# Shield_Amir_EDO_V_0_2_1.net
KiCad netlist of a schematic drawn in EasyEDA
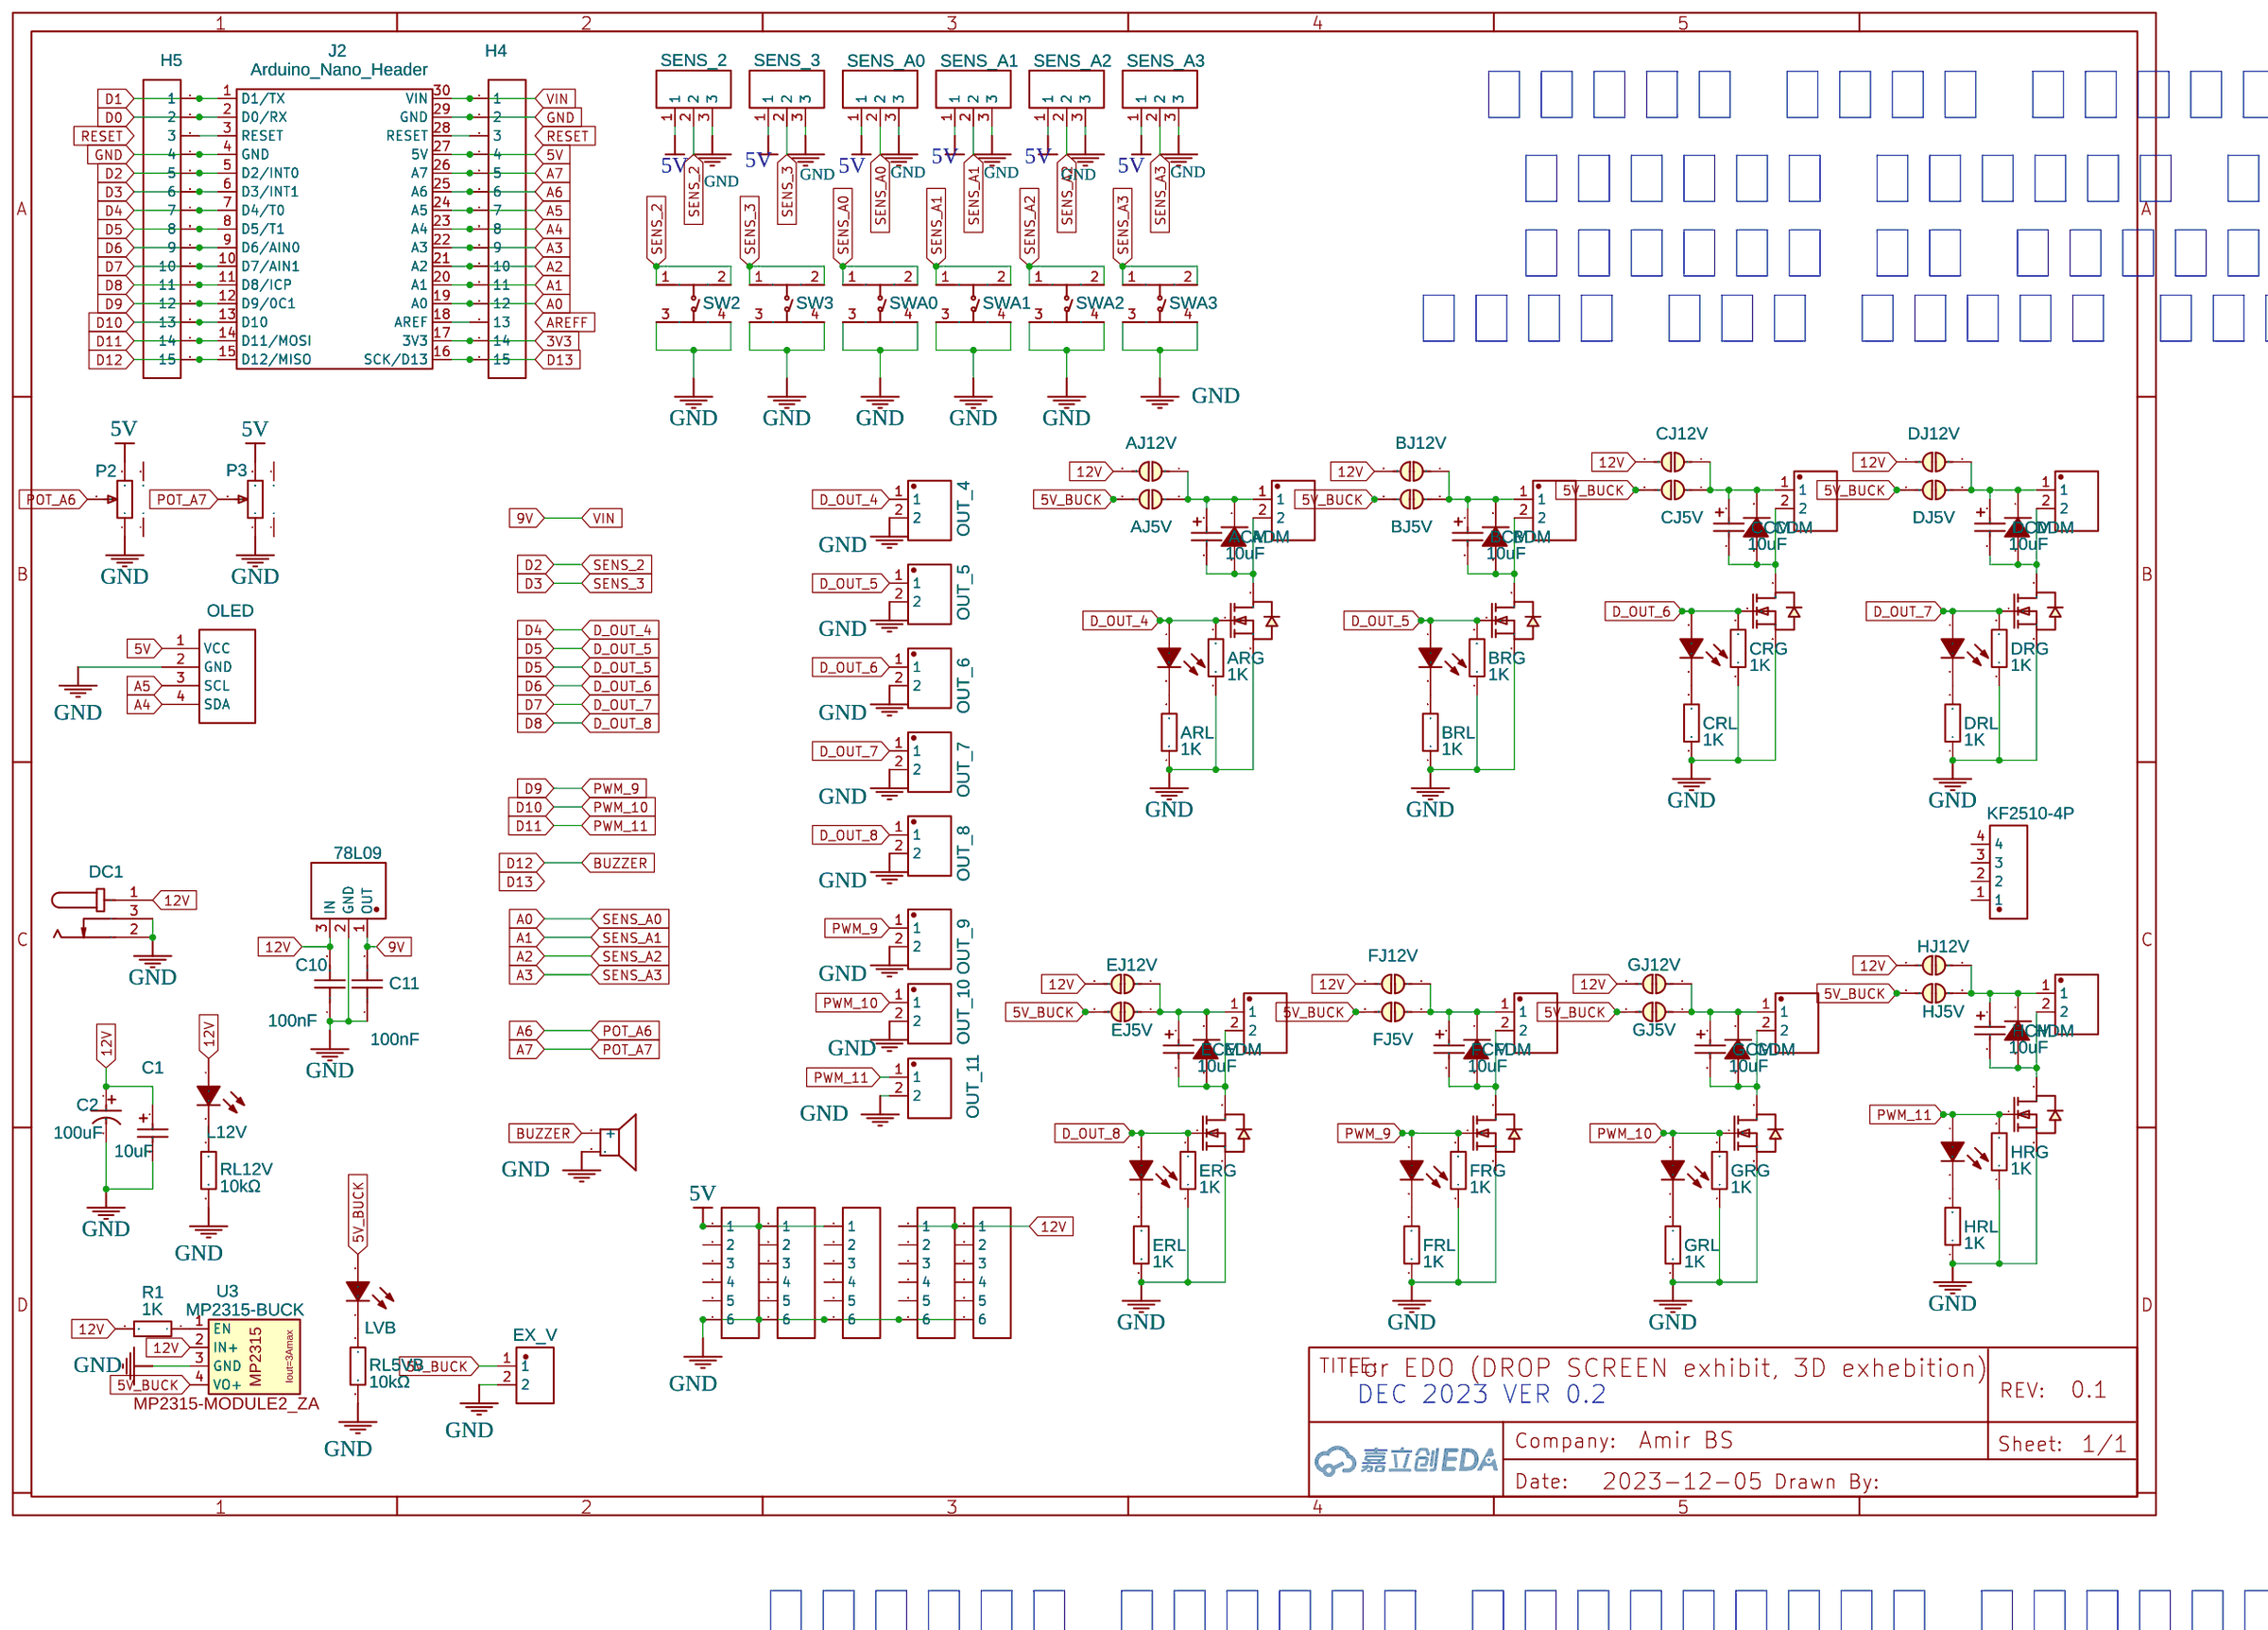
[diagram p0: schematic sheet]

(export (version "E")
  (design (tool "Eeschema 10.0.6"))
  (components
    (comp (ref "ACM")
      (value "10uF")
      (fields (field (name "Manufacturer Part") "TAJA106K016RNJ") (field (name "Manufacturer") "Kyocera AVX"))
      (libsource (lib "") (part "TAJA106K016RNJ"))
    )
    (comp (ref "ACON")
      (value "KF2510-2A")
      (fields (field (name "BOM_Supplier Part") "C27543"))
      (libsource (lib "") (part "KF2510-2A_5"))
    )
    (comp (ref "ADM")
      (value "1N4007")
      (fields (field (name "BOM_Manufacturer Part") "1N4007F") (field (name "BOM_Supplier Part") "C110856"))
      (libsource (lib "") (part "1N4007F_4"))
    )
    (comp (ref "AJ5V") (value "JUMPER-SMT_2") (libsource (lib "") (part "JUMPER-SMT_2_1")))
    (comp (ref "AJ12V") (value "JUMPER-SMT_2") (libsource (lib "") (part "JUMPER-SMT_2_3")))
    (comp (ref "ALD")
      (value "LED")
      (fields
        (field (name "BOM_Manufacturer Part") "19-217/BHC-ZL1M2RY/3T")
        (field (name "BOM_Supplier Part") "C72041")
      )
      (libsource (lib "") (part "19-217/BHC-ZL1M2RY/3T_3"))
    )
    (comp (ref "AQ")
      (value "Q")
      (fields (field (name "BOM_Manufacturer Part") "AO3400") (field (name "BOM_Supplier Part") "C5224189"))
      (libsource (lib "") (part "JSM2302_2"))
    )
    (comp (ref "ARG")
      (value "1K")
      (fields
        (field (name "BOM_Manufacturer Part") "0603WAF1001T5E")
        (field (name "BOM_Supplier Part") "C21190")
      )
      (libsource (lib "") (part "0603WAF1001T5E_13"))
    )
    (comp (ref "ARL")
      (value "1K")
      (fields
        (field (name "BOM_Manufacturer Part") "0603WAF1001T5E")
        (field (name "BOM_Supplier Part") "C21190")
      )
      (libsource (lib "") (part "0603WAF1001T5E_5"))
    )
    (comp (ref "BCM")
      (value "10uF")
      (fields (field (name "Manufacturer Part") "TAJA106K016RNJ") (field (name "Manufacturer") "Kyocera AVX"))
      (libsource (lib "") (part "TAJA106K016RNJ_3"))
    )
    (comp (ref "BCON")
      (value "KF2510-2A")
      (fields (field (name "BOM_Supplier Part") "C27543"))
      (libsource (lib "") (part "KF2510-2A_1"))
    )
    (comp (ref "BDM")
      (value "1N4007")
      (fields (field (name "BOM_Manufacturer Part") "1N4007F") (field (name "BOM_Supplier Part") "C110856"))
      (libsource (lib "") (part "1N4007F_3"))
    )
    (comp (ref "BJ5V") (value "JUMPER-SMT_2") (libsource (lib "") (part "JUMPER-SMT_2_6")))
    (comp (ref "BJ12V") (value "JUMPER-SMT_2") (libsource (lib "") (part "JUMPER-SMT_2_8")))
    (comp (ref "BLD")
      (value "LED")
      (fields
        (field (name "BOM_Manufacturer Part") "19-217/BHC-ZL1M2RY/3T")
        (field (name "BOM_Supplier Part") "C72041")
      )
      (libsource (lib "") (part "19-217/BHC-ZL1M2RY/3T_5"))
    )
    (comp (ref "BQ")
      (value "Q")
      (fields (field (name "BOM_Manufacturer Part") "AO3400") (field (name "BOM_Supplier Part") "C5224189"))
      (libsource (lib "") (part "JSM2302"))
    )
    (comp (ref "BRG")
      (value "1K")
      (fields
        (field (name "BOM_Manufacturer Part") "0603WAF1001T5E")
        (field (name "BOM_Supplier Part") "C21190")
      )
      (libsource (lib "") (part "0603WAF1001T5E_9"))
    )
    (comp (ref "BRL")
      (value "1K")
      (fields
        (field (name "BOM_Manufacturer Part") "0603WAF1001T5E")
        (field (name "BOM_Supplier Part") "C21190")
      )
      (libsource (lib "") (part "0603WAF1001T5E_12"))
    )
    (comp (ref "BUZZER1")
      (value "BUZZER-12X9")
      (fields (field (name "Manufacturer Part") "buzzer-12X9"))
      (libsource (lib "") (part "BUZZER-12X9"))
    )
    (comp (ref "C1")
      (value "10uF")
      (fields (field (name "Manufacturer Part") "TAJA106K016RNJ") (field (name "Manufacturer") "Kyocera AVX"))
      (libsource (lib "") (part "TAJA106K016RNJ_4"))
    )
    (comp (ref "C2")
      (value "100uF")
      (fields
        (field (name "Manufacturer Part") "KM107M035E11RR0VH2FP0")
        (field (name "Manufacturer") "CX(承兴)")
      )
      (libsource (lib "") (part "100uF 35V 6.3*11"))
    )
    (comp (ref "C10")
      (value "100nF")
      (fields
        (field (name "Manufacturer Part") "CC0603KRX7R9BB104")
        (field (name "Manufacturer") "YAGEO(国巨)")
      )
      (libsource (lib "") (part "CC0603KRX7R9BB104"))
    )
    (comp (ref "C11")
      (value "100nF")
      (fields
        (field (name "Manufacturer Part") "CC0603KRX7R9BB104")
        (field (name "Manufacturer") "YAGEO(国巨)")
      )
      (libsource (lib "") (part "CC0603KRX7R9BB104"))
    )
    (comp (ref "CCM")
      (value "10uF")
      (fields (field (name "Manufacturer Part") "TAJA106K016RNJ") (field (name "Manufacturer") "Kyocera AVX"))
      (libsource (lib "") (part "TAJA106K016RNJ_8"))
    )
    (comp (ref "CCON")
      (value "KF2510-2A")
      (fields (field (name "BOM_Supplier Part") "C27543"))
      (libsource (lib "") (part "KF2510-2A"))
    )
    (comp (ref "CDM")
      (value "1N4007")
      (fields (field (name "BOM_Manufacturer Part") "1N4007F") (field (name "BOM_Supplier Part") "C110856"))
      (libsource (lib "") (part "1N4007F_1"))
    )
    (comp (ref "CJ5V") (value "JUMPER-SMT_2") (libsource (lib "") (part "JUMPER-SMT_2_15")))
    (comp (ref "CJ12V") (value "JUMPER-SMT_2") (libsource (lib "") (part "JUMPER-SMT_2")))
    (comp (ref "CLD")
      (value "LED")
      (fields
        (field (name "BOM_Manufacturer Part") "19-217/BHC-ZL1M2RY/3T")
        (field (name "BOM_Supplier Part") "C72041")
      )
      (libsource (lib "") (part "19-217/BHC-ZL1M2RY/3T_2"))
    )
    (comp (ref "CQ")
      (value "Q")
      (fields (field (name "BOM_Manufacturer Part") "AO3400") (field (name "BOM_Supplier Part") "C5224189"))
      (libsource (lib "") (part "JSM2302_1"))
    )
    (comp (ref "CRG")
      (value "1K")
      (fields
        (field (name "BOM_Manufacturer Part") "0603WAF1001T5E")
        (field (name "BOM_Supplier Part") "C21190")
      )
      (libsource (lib "") (part "0603WAF1001T5E_16"))
    )
    (comp (ref "CRL")
      (value "1K")
      (fields
        (field (name "BOM_Manufacturer Part") "0603WAF1001T5E")
        (field (name "BOM_Supplier Part") "C21190")
      )
      (libsource (lib "") (part "0603WAF1001T5E_15"))
    )
    (comp (ref "DC1")
      (value "DC")
      (fields
        (field (name "BOM_Manufacturer Part") "DC005-2.0MM")
        (field (name "BOM_Supplier Part") "C111567")
      )
      (libsource (lib "") (part "DC005-2.0MM"))
    )
    (comp (ref "DCM")
      (value "10uF")
      (fields (field (name "Manufacturer Part") "TAJA106K016RNJ") (field (name "Manufacturer") "Kyocera AVX"))
      (libsource (lib "") (part "TAJA106K016RNJ_1"))
    )
    (comp (ref "DCON")
      (value "KF2510-2A")
      (fields (field (name "BOM_Supplier Part") "C27543"))
      (libsource (lib "") (part "KF2510-2A_3"))
    )
    (comp (ref "DDM")
      (value "1N4007")
      (fields (field (name "BOM_Manufacturer Part") "1N4007F") (field (name "BOM_Supplier Part") "C110856"))
      (libsource (lib "") (part "1N4007F_2"))
    )
    (comp (ref "DJ5V") (value "JUMPER-SMT_2") (libsource (lib "") (part "JUMPER-SMT_2_12")))
    (comp (ref "DJ12V") (value "JUMPER-SMT_2") (libsource (lib "") (part "JUMPER-SMT_2_7")))
    (comp (ref "DLD")
      (value "LED")
      (fields
        (field (name "BOM_Manufacturer Part") "19-217/BHC-ZL1M2RY/3T")
        (field (name "BOM_Supplier Part") "C72041")
      )
      (libsource (lib "") (part "19-217/BHC-ZL1M2RY/3T_6"))
    )
    (comp (ref "DQ")
      (value "Q")
      (fields (field (name "BOM_Manufacturer Part") "AO3400") (field (name "BOM_Supplier Part") "C5224189"))
      (libsource (lib "") (part "JSM2302_7"))
    )
    (comp (ref "DRG")
      (value "1K")
      (fields
        (field (name "BOM_Manufacturer Part") "0603WAF1001T5E")
        (field (name "BOM_Supplier Part") "C21190")
      )
      (libsource (lib "") (part "0603WAF1001T5E_6"))
    )
    (comp (ref "DRL")
      (value "1K")
      (fields
        (field (name "BOM_Manufacturer Part") "0603WAF1001T5E")
        (field (name "BOM_Supplier Part") "C21190")
      )
      (libsource (lib "") (part "0603WAF1001T5E_10"))
    )
    (comp (ref "ECM")
      (value "10uF")
      (fields (field (name "Manufacturer Part") "TAJA106K016RNJ") (field (name "Manufacturer") "Kyocera AVX"))
      (libsource (lib "") (part "TAJA106K016RNJ_7"))
    )
    (comp (ref "ECON")
      (value "KF2510-2A")
      (fields (field (name "BOM_Supplier Part") "C27543"))
      (libsource (lib "") (part "KF2510-2A_6"))
    )
    (comp (ref "EDM")
      (value "1N4007")
      (fields (field (name "BOM_Manufacturer Part") "1N4007F") (field (name "BOM_Supplier Part") "C110856"))
      (libsource (lib "") (part "1N4007F_5"))
    )
    (comp (ref "EJ5V") (value "JUMPER-SMT_2") (libsource (lib "") (part "JUMPER-SMT_2_11")))
    (comp (ref "EJ12V") (value "JUMPER-SMT_2") (libsource (lib "") (part "JUMPER-SMT_2_2")))
    (comp (ref "ELD")
      (value "LED")
      (fields
        (field (name "BOM_Manufacturer Part") "19-217/BHC-ZL1M2RY/3T")
        (field (name "BOM_Supplier Part") "C72041")
      )
      (libsource (lib "") (part "19-217/BHC-ZL1M2RY/3T_9"))
    )
    (comp (ref "EQ")
      (value "Q")
      (fields (field (name "BOM_Manufacturer Part") "AO3400") (field (name "BOM_Supplier Part") "C5224189"))
      (libsource (lib "") (part "JSM2302_4"))
    )
    (comp (ref "ERG")
      (value "1K")
      (fields
        (field (name "BOM_Manufacturer Part") "0603WAF1001T5E")
        (field (name "BOM_Supplier Part") "C21190")
      )
      (libsource (lib "") (part "0603WAF1001T5E_8"))
    )
    (comp (ref "ERL")
      (value "1K")
      (fields
        (field (name "BOM_Manufacturer Part") "0603WAF1001T5E")
        (field (name "BOM_Supplier Part") "C21190")
      )
      (libsource (lib "") (part "0603WAF1001T5E_4"))
    )
    (comp (ref "EX_V")
      (value "EX_V")
      (fields
        (field (name "Manufacturer Part") "WJ306V-5.0-2P-14-00A")
        (field (name "Manufacturer") "KANGNEX(康奈克斯电气)")
      )
      (libsource (lib "") (part "WJ306V-5.0-2P-14-00A"))
    )
    (comp (ref "FCM")
      (value "10uF")
      (fields (field (name "Manufacturer Part") "TAJA106K016RNJ") (field (name "Manufacturer") "Kyocera AVX"))
      (libsource (lib "") (part "TAJA106K016RNJ_2"))
    )
    (comp (ref "FCON")
      (value "KF2510-2A")
      (fields (field (name "BOM_Supplier Part") "C27543"))
      (libsource (lib "") (part "KF2510-2A_8"))
    )
    (comp (ref "FDM")
      (value "1N4007")
      (fields (field (name "BOM_Manufacturer Part") "1N4007F") (field (name "BOM_Supplier Part") "C110856"))
      (libsource (lib "") (part "1N4007F_6"))
    )
    (comp (ref "FJ5V") (value "JUMPER-SMT_2") (libsource (lib "") (part "JUMPER-SMT_2_10")))
    (comp (ref "FJ12V") (value "JUMPER-SMT_2") (libsource (lib "") (part "JUMPER-SMT_2_4")))
    (comp (ref "FLD")
      (value "LED")
      (fields
        (field (name "BOM_Manufacturer Part") "19-217/BHC-ZL1M2RY/3T")
        (field (name "BOM_Supplier Part") "C72041")
      )
      (libsource (lib "") (part "19-217/BHC-ZL1M2RY/3T"))
    )
    (comp (ref "FQ")
      (value "Q")
      (fields (field (name "BOM_Manufacturer Part") "AO3400") (field (name "BOM_Supplier Part") "C5224189"))
      (libsource (lib "") (part "JSM2302_6"))
    )
    (comp (ref "FRG")
      (value "1K")
      (fields
        (field (name "BOM_Manufacturer Part") "0603WAF1001T5E")
        (field (name "BOM_Supplier Part") "C21190")
      )
      (libsource (lib "") (part "0603WAF1001T5E_11"))
    )
    (comp (ref "FRL")
      (value "1K")
      (fields
        (field (name "BOM_Manufacturer Part") "0603WAF1001T5E")
        (field (name "BOM_Supplier Part") "C21190")
      )
      (libsource (lib "") (part "0603WAF1001T5E_1"))
    )
    (comp (ref "GCM")
      (value "10uF")
      (fields (field (name "Manufacturer Part") "TAJA106K016RNJ") (field (name "Manufacturer") "Kyocera AVX"))
      (libsource (lib "") (part "TAJA106K016RNJ_6"))
    )
    (comp (ref "GCON")
      (value "KF2510-2A")
      (fields (field (name "BOM_Supplier Part") "C27543"))
      (libsource (lib "") (part "KF2510-2A_4"))
    )
    (comp (ref "GDM")
      (value "1N4007")
      (fields (field (name "BOM_Manufacturer Part") "1N4007F") (field (name "BOM_Supplier Part") "C110856"))
      (libsource (lib "") (part "1N4007F"))
    )
    (comp (ref "GJ5V") (value "JUMPER-SMT_2") (libsource (lib "") (part "JUMPER-SMT_2_13")))
    (comp (ref "GJ12V") (value "JUMPER-SMT_2") (libsource (lib "") (part "JUMPER-SMT_2_9")))
    (comp (ref "GLD")
      (value "LED")
      (fields
        (field (name "BOM_Manufacturer Part") "19-217/BHC-ZL1M2RY/3T")
        (field (name "BOM_Supplier Part") "C72041")
      )
      (libsource (lib "") (part "19-217/BHC-ZL1M2RY/3T_7"))
    )
    (comp (ref "GQ")
      (value "Q")
      (fields (field (name "BOM_Manufacturer Part") "AO3400") (field (name "BOM_Supplier Part") "C5224189"))
      (libsource (lib "") (part "JSM2302_3"))
    )
    (comp (ref "GRG")
      (value "1K")
      (fields
        (field (name "BOM_Manufacturer Part") "0603WAF1001T5E")
        (field (name "BOM_Supplier Part") "C21190")
      )
      (libsource (lib "") (part "0603WAF1001T5E"))
    )
    (comp (ref "GRL")
      (value "1K")
      (fields
        (field (name "BOM_Manufacturer Part") "0603WAF1001T5E")
        (field (name "BOM_Supplier Part") "C21190")
      )
      (libsource (lib "") (part "0603WAF1001T5E_2"))
    )
    (comp (ref "H1")
      (value "HDR-F-2.54_1x6")
      (fields (field (name "BOM_Supplier Part") "C40877"))
      (libsource (lib "") (part "HDR-F-2.54_1x6"))
    )
    (comp (ref "H2")
      (value "HDR-F-2.54_1x6")
      (fields (field (name "BOM_Supplier Part") "C40877"))
      (libsource (lib "") (part "HDR-F-2.54_1x6"))
    )
    (comp (ref "H3")
      (value "HDR-F-2.54_1x6")
      (fields (field (name "BOM_Supplier Part") "C40877"))
      (libsource (lib "") (part "HDR-F-2.54_1x6"))
    )
    (comp (ref "H4")
      (value "HDR-F-2.54_1x15")
      (fields (field (name "BOM_Supplier Part") "C124408"))
      (libsource (lib "") (part "HDR-F-2.54_1x15"))
    )
    (comp (ref "H5")
      (value "HDR-F-2.54_1x15")
      (fields (field (name "BOM_Supplier Part") "C124408"))
      (libsource (lib "") (part "HDR-F-2.54_1x15_1"))
    )
    (comp (ref "H6")
      (value "HDR-F-2.54_1x6")
      (fields (field (name "BOM_Supplier Part") "C40877"))
      (libsource (lib "") (part "HDR-F-2.54_1x6"))
    )
    (comp (ref "H11")
      (value "HDR-F-2.54_1x6")
      (fields (field (name "BOM_Supplier Part") "C40877"))
      (libsource (lib "") (part "HDR-F-2.54_1x6"))
    )
    (comp (ref "HCM")
      (value "10uF")
      (fields (field (name "Manufacturer Part") "TAJA106K016RNJ") (field (name "Manufacturer") "Kyocera AVX"))
      (libsource (lib "") (part "TAJA106K016RNJ_5"))
    )
    (comp (ref "HCON")
      (value "KF2510-2A")
      (fields (field (name "BOM_Supplier Part") "C27543"))
      (libsource (lib "") (part "KF2510-2A_7"))
    )
    (comp (ref "HDM")
      (value "1N4007")
      (fields (field (name "BOM_Manufacturer Part") "1N4007F") (field (name "BOM_Supplier Part") "C110856"))
      (libsource (lib "") (part "1N4007F_7"))
    )
    (comp (ref "HJ5V") (value "JUMPER-SMT_2") (libsource (lib "") (part "JUMPER-SMT_2_5")))
    (comp (ref "HJ12V") (value "JUMPER-SMT_2") (libsource (lib "") (part "JUMPER-SMT_2_14")))
    (comp (ref "HLD")
      (value "LED")
      (fields
        (field (name "BOM_Manufacturer Part") "19-217/BHC-ZL1M2RY/3T")
        (field (name "BOM_Supplier Part") "C72041")
      )
      (libsource (lib "") (part "19-217/BHC-ZL1M2RY/3T_4"))
    )
    (comp (ref "HQ")
      (value "Q")
      (fields (field (name "BOM_Manufacturer Part") "AO3400") (field (name "BOM_Supplier Part") "C5224189"))
      (libsource (lib "") (part "JSM2302_5"))
    )
    (comp (ref "HRG")
      (value "1K")
      (fields
        (field (name "BOM_Manufacturer Part") "0603WAF1001T5E")
        (field (name "BOM_Supplier Part") "C21190")
      )
      (libsource (lib "") (part "0603WAF1001T5E_7"))
    )
    (comp (ref "HRL")
      (value "1K")
      (fields
        (field (name "BOM_Manufacturer Part") "0603WAF1001T5E")
        (field (name "BOM_Supplier Part") "C21190")
      )
      (libsource (lib "") (part "0603WAF1001T5E_14"))
    )
    (comp (ref "J2") (value "Arduino_Nano_Header") (libsource (lib "") (part "Arduino_Nano_Header")))
    (comp (ref "L12V")
      (value "LED")
      (fields
        (field (name "BOM_Manufacturer Part") "19-217/BHC-ZL1M2RY/3T")
        (field (name "BOM_Supplier Part") "C72041")
      )
      (libsource (lib "") (part "19-217/BHC-ZL1M2RY/3T_1"))
    )
    (comp (ref "LVB")
      (value "LED")
      (fields
        (field (name "BOM_Manufacturer Part") "19-217/BHC-ZL1M2RY/3T")
        (field (name "BOM_Supplier Part") "C72041")
      )
      (libsource (lib "") (part "19-217/BHC-ZL1M2RY/3T_8"))
    )
    (comp (ref "OLED")
      (value "1.3 inch OLED SSH1106 I2C 128x64 copy")
      (libsource (lib "") (part "1.3 inch OLED SSH1106 I2C 128x64 copy"))
    )
    (comp (ref "OUT_4")
      (value "KF2510-2A")
      (fields (field (name "BOM_Supplier Part") "C27543"))
      (libsource (lib "") (part "KF2510-2A_2"))
    )
    (comp (ref "OUT_5")
      (value "KF2510-2A")
      (fields (field (name "BOM_Supplier Part") "C27543"))
      (libsource (lib "") (part "KF2510-2A_2"))
    )
    (comp (ref "OUT_6")
      (value "KF2510-2A")
      (fields (field (name "BOM_Supplier Part") "C27543"))
      (libsource (lib "") (part "KF2510-2A_2"))
    )
    (comp (ref "OUT_7")
      (value "KF2510-2A")
      (fields (field (name "BOM_Supplier Part") "C27543"))
      (libsource (lib "") (part "KF2510-2A_2"))
    )
    (comp (ref "OUT_8")
      (value "KF2510-2A")
      (fields (field (name "BOM_Supplier Part") "C27543"))
      (libsource (lib "") (part "KF2510-2A_2"))
    )
    (comp (ref "OUT_9")
      (value "KF2510-2A")
      (fields (field (name "BOM_Supplier Part") "C27543"))
      (libsource (lib "") (part "KF2510-2A_2"))
    )
    (comp (ref "OUT_10")
      (value "KF2510-2A")
      (fields (field (name "BOM_Supplier Part") "C27543"))
      (libsource (lib "") (part "KF2510-2A_2"))
    )
    (comp (ref "OUT_11")
      (value "KF2510-2A")
      (fields (field (name "BOM_Supplier Part") "C27543"))
      (libsource (lib "") (part "KF2510-2A_2"))
    )
    (comp (ref "P2")
      (value "长柄旋转电位器")
      (fields (field (name "BOM_Supplier Part") "C2874842"))
      (libsource (lib "") (part "长柄旋转电位器"))
    )
    (comp (ref "P3")
      (value "长柄旋转电位器")
      (fields (field (name "BOM_Supplier Part") "C2874842"))
      (libsource (lib "") (part "长柄旋转电位器"))
    )
    (comp (ref "R1")
      (value "1K")
      (fields
        (field (name "BOM_Manufacturer Part") "0603WAF1001T5E")
        (field (name "BOM_Supplier Part") "C21190")
      )
      (libsource (lib "") (part "0603WAF1001T5E_3"))
    )
    (comp (ref "RL5VB")
      (value "10kΩ")
      (fields
        (field (name "BOM_Manufacturer Part") "0603WAF1002T5E")
        (field (name "BOM_Supplier Part") "C25804")
      )
      (libsource (lib "") (part "0603WAF1002T5E_1"))
    )
    (comp (ref "RL12V")
      (value "10kΩ")
      (fields
        (field (name "BOM_Manufacturer Part") "0603WAF1002T5E")
        (field (name "BOM_Supplier Part") "C25804")
      )
      (libsource (lib "") (part "0603WAF1002T5E"))
    )
    (comp (ref "SENS_2")
      (value "FK2510")
      (fields (field (name "Manufacturer Part") "2510-3A") (field (name "Manufacturer") "BOOMELE(博穆精密)"))
      (libsource (lib "") (part "kf2510_3A_1"))
    )
    (comp (ref "SENS_3")
      (value "FK2510")
      (fields (field (name "Manufacturer Part") "2510-3A") (field (name "Manufacturer") "BOOMELE(博穆精密)"))
      (libsource (lib "") (part "kf2510_3A_1"))
    )
    (comp (ref "SENS_A0")
      (value "FK2510")
      (fields (field (name "Manufacturer Part") "2510-3A") (field (name "Manufacturer") "BOOMELE(博穆精密)"))
      (libsource (lib "") (part "kf2510_3A"))
    )
    (comp (ref "SENS_A1")
      (value "FK2510")
      (fields (field (name "Manufacturer Part") "2510-3A") (field (name "Manufacturer") "BOOMELE(博穆精密)"))
      (libsource (lib "") (part "kf2510_3A"))
    )
    (comp (ref "SENS_A2")
      (value "FK2510")
      (fields (field (name "Manufacturer Part") "2510-3A") (field (name "Manufacturer") "BOOMELE(博穆精密)"))
      (libsource (lib "") (part "kf2510_3A"))
    )
    (comp (ref "SENS_A3")
      (value "FK2510")
      (fields (field (name "Manufacturer Part") "2510-3A") (field (name "Manufacturer") "BOOMELE(博穆精密)"))
      (libsource (lib "") (part "kf2510_3A"))
    )
    (comp (ref "SW2")
      (value "TC-6610-7-160G")
      (fields (field (name "Manufacturer") "HCTL(华灿天禄)"))
      (libsource (lib "") (part "TC-6610-7-160G_1"))
    )
    (comp (ref "SW3")
      (value "TC-6610-7-160G")
      (fields (field (name "Manufacturer") "HCTL(华灿天禄)"))
      (libsource (lib "") (part "TC-6610-7-160G_1"))
    )
    (comp (ref "SWA0")
      (value "TC-6610-7-160G")
      (fields (field (name "Manufacturer") "HCTL(华灿天禄)"))
      (libsource (lib "") (part "TC-6610-7-160G"))
    )
    (comp (ref "SWA1")
      (value "TC-6610-7-160G")
      (fields (field (name "Manufacturer") "HCTL(华灿天禄)"))
      (libsource (lib "") (part "TC-6610-7-160G"))
    )
    (comp (ref "SWA2")
      (value "TC-6610-7-160G")
      (fields (field (name "Manufacturer") "HCTL(华灿天禄)"))
      (libsource (lib "") (part "TC-6610-7-160G"))
    )
    (comp (ref "SWA3")
      (value "TC-6610-7-160G")
      (fields (field (name "Manufacturer") "HCTL(华灿天禄)"))
      (libsource (lib "") (part "TC-6610-7-160G"))
    )
    (comp (ref "U1")
      (value "KF2510-4P")
      (fields (field (name "BOM_Supplier Part") "C9900008392"))
      (libsource (lib "") (part "KF2510-4P"))
    )
    (comp (ref "U3") (value "MP2315-BUCK") (libsource (lib "") (part "MP2315-BUCK")))
    (comp (ref "U5")
      (value "78L09")
      (fields (field (name "Manufacturer Part") "78L09U 78L09") (field (name "Manufacturer") "CBI(创基)"))
      (libsource (lib "") (part "78L09U 78L09"))
    )
  )
  (nets
    (net (code "1") (name "3V3") (class "Default")
      (node (ref "H4") (pin "14") (pinfunction "14_14") (pintype "unspecified"))
      (node (ref "J2") (pin "17") (pinfunction "3V3_17") (pintype "unspecified"))
    )
    (net (code "2") (name "5V") (class "Default")
      (node (ref "H1") (pin "1") (pinfunction "1_1") (pintype "input"))
      (node (ref "H2") (pin "1") (pinfunction "1_1") (pintype "input"))
      (node (ref "H3") (pin "1") (pinfunction "1_1") (pintype "input"))
      (node (ref "H4") (pin "4") (pinfunction "4_4") (pintype "unspecified"))
      (node (ref "J2") (pin "27") (pinfunction "5V_27") (pintype "unspecified"))
      (node (ref "OLED") (pin "1") (pinfunction "VCC_1") (pintype "passive"))
      (node (ref "P2") (pin "3") (pinfunction "3_3") (pintype "input"))
      (node (ref "P3") (pin "3") (pinfunction "3_3") (pintype "input"))
      (node (ref "SENS_2") (pin "1") (pinfunction "1_1") (pintype "unspecified"))
      (node (ref "SENS_3") (pin "1") (pinfunction "1_1") (pintype "unspecified"))
      (node (ref "SENS_A0") (pin "1") (pinfunction "1_1") (pintype "unspecified"))
      (node (ref "SENS_A1") (pin "1") (pinfunction "1_1") (pintype "unspecified"))
      (node (ref "SENS_A2") (pin "1") (pinfunction "1_1") (pintype "unspecified"))
      (node (ref "SENS_A3") (pin "1") (pinfunction "1_1") (pintype "unspecified"))
    )
    (net (code "3") (name "5V_BUCK") (class "Default")
      (node (ref "AJ5V") (pin "2") (pinfunction "2_2") (pintype "bidirectional"))
      (node (ref "BJ5V") (pin "2") (pinfunction "2_2") (pintype "bidirectional"))
      (node (ref "CJ5V") (pin "2") (pinfunction "2_2") (pintype "bidirectional"))
      (node (ref "DJ5V") (pin "2") (pinfunction "2_2") (pintype "bidirectional"))
      (node (ref "EJ5V") (pin "2") (pinfunction "2_2") (pintype "bidirectional"))
      (node (ref "EX_V") (pin "1") (pinfunction "1_1") (pintype "unspecified"))
      (node (ref "FJ5V") (pin "2") (pinfunction "2_2") (pintype "bidirectional"))
      (node (ref "GJ5V") (pin "2") (pinfunction "2_2") (pintype "bidirectional"))
      (node (ref "HJ5V") (pin "2") (pinfunction "2_2") (pintype "bidirectional"))
      (node (ref "LVB") (pin "1") (pinfunction "A_1") (pintype "input"))
      (node (ref "U3") (pin "4") (pinfunction "VO+_4") (pintype "unspecified"))
    )
    (net (code "4") (name "9V") (class "Default")
      (node (ref "C11") (pin "2") (pinfunction "2_2") (pintype "unspecified"))
      (node (ref "H4") (pin "1") (pinfunction "1_1") (pintype "unspecified"))
      (node (ref "J2") (pin "30") (pinfunction "VIN_30") (pintype "unspecified"))
      (node (ref "U5") (pin "1") (pinfunction "OUT_1") (pintype "unspecified"))
    )
    (net (code "5") (name "12V") (class "Default")
      (node (ref "AJ12V") (pin "2") (pinfunction "2_2") (pintype "bidirectional"))
      (node (ref "BJ12V") (pin "2") (pinfunction "2_2") (pintype "bidirectional"))
      (node (ref "C1") (pin "1") (pinfunction "1_1") (pintype "input"))
      (node (ref "C10") (pin "2") (pinfunction "2_2") (pintype "unspecified"))
      (node (ref "C2") (pin "1") (pinfunction "1_1") (pintype "input"))
      (node (ref "CJ12V") (pin "2") (pinfunction "2_2") (pintype "bidirectional"))
      (node (ref "DC1") (pin "1") (pinfunction "1_1") (pintype "unspecified"))
      (node (ref "DJ12V") (pin "2") (pinfunction "2_2") (pintype "bidirectional"))
      (node (ref "EJ12V") (pin "2") (pinfunction "2_2") (pintype "bidirectional"))
      (node (ref "FJ12V") (pin "2") (pinfunction "2_2") (pintype "bidirectional"))
      (node (ref "GJ12V") (pin "2") (pinfunction "2_2") (pintype "bidirectional"))
      (node (ref "H11") (pin "1") (pinfunction "1_1") (pintype "input"))
      (node (ref "H6") (pin "1") (pinfunction "1_1") (pintype "input"))
      (node (ref "HJ12V") (pin "2") (pinfunction "2_2") (pintype "bidirectional"))
      (node (ref "L12V") (pin "1") (pinfunction "A_1") (pintype "input"))
      (node (ref "R1") (pin "2") (pinfunction "2_2") (pintype "input"))
      (node (ref "U3") (pin "2") (pinfunction "IN+_2") (pintype "unspecified"))
      (node (ref "U5") (pin "3") (pinfunction "IN_3") (pintype "unspecified"))
    )
    (net (code "6") (name "A0") (class "Default")
      (node (ref "H4") (pin "12") (pinfunction "12_12") (pintype "unspecified"))
      (node (ref "J2") (pin "19") (pinfunction "A0_19") (pintype "unspecified"))
      (node (ref "SENS_A0") (pin "2") (pinfunction "2_2") (pintype "unspecified"))
      (node (ref "SWA0") (pin "1") (pinfunction "1_1") (pintype "unspecified"))
      (node (ref "SWA0") (pin "2") (pinfunction "2_2") (pintype "unspecified"))
    )
    (net (code "7") (name "A1") (class "Default")
      (node (ref "H4") (pin "11") (pinfunction "11_11") (pintype "unspecified"))
      (node (ref "J2") (pin "20") (pinfunction "A1_20") (pintype "unspecified"))
      (node (ref "SENS_A1") (pin "2") (pinfunction "2_2") (pintype "unspecified"))
      (node (ref "SWA1") (pin "1") (pinfunction "1_1") (pintype "unspecified"))
      (node (ref "SWA1") (pin "2") (pinfunction "2_2") (pintype "unspecified"))
    )
    (net (code "8") (name "A2") (class "Default")
      (node (ref "H4") (pin "10") (pinfunction "10_10") (pintype "unspecified"))
      (node (ref "J2") (pin "21") (pinfunction "A2_21") (pintype "unspecified"))
      (node (ref "SENS_A2") (pin "2") (pinfunction "2_2") (pintype "unspecified"))
      (node (ref "SWA2") (pin "1") (pinfunction "1_1") (pintype "unspecified"))
      (node (ref "SWA2") (pin "2") (pinfunction "2_2") (pintype "unspecified"))
    )
    (net (code "9") (name "A3") (class "Default")
      (node (ref "H4") (pin "9") (pinfunction "9_9") (pintype "unspecified"))
      (node (ref "J2") (pin "22") (pinfunction "A3_22") (pintype "unspecified"))
      (node (ref "SENS_A3") (pin "2") (pinfunction "2_2") (pintype "unspecified"))
      (node (ref "SWA3") (pin "1") (pinfunction "1_1") (pintype "unspecified"))
      (node (ref "SWA3") (pin "2") (pinfunction "2_2") (pintype "unspecified"))
    )
    (net (code "10") (name "A4") (class "Default")
      (node (ref "H4") (pin "8") (pinfunction "8_8") (pintype "unspecified"))
      (node (ref "J2") (pin "23") (pinfunction "A4_23") (pintype "unspecified"))
      (node (ref "OLED") (pin "4") (pinfunction "SDA_4") (pintype "bidirectional"))
    )
    (net (code "11") (name "A5") (class "Default")
      (node (ref "H4") (pin "7") (pinfunction "7_7") (pintype "unspecified"))
      (node (ref "J2") (pin "24") (pinfunction "A5_24") (pintype "unspecified"))
      (node (ref "OLED") (pin "3") (pinfunction "SCL_3") (pintype "bidirectional"))
    )
    (net (code "12") (name "A6") (class "Default")
      (node (ref "H4") (pin "6") (pinfunction "6_6") (pintype "unspecified"))
      (node (ref "J2") (pin "25") (pinfunction "A6_25") (pintype "unspecified"))
      (node (ref "P2") (pin "2") (pinfunction "2_2") (pintype "input"))
    )
    (net (code "13") (name "A7") (class "Default")
      (node (ref "H4") (pin "5") (pinfunction "5_5") (pintype "unspecified"))
      (node (ref "J2") (pin "26") (pinfunction "A7_26") (pintype "unspecified"))
      (node (ref "P3") (pin "2") (pinfunction "2_2") (pintype "input"))
    )
    (net (code "15") (name "BUZZER") (class "Default")
      (node (ref "BUZZER1") (pin "1") (pinfunction "+_1") (pintype "unspecified"))
      (node (ref "H5") (pin "15") (pinfunction "15_15") (pintype "unspecified"))
      (node (ref "J2") (pin "15") (pinfunction "D12/MISO_15") (pintype "unspecified"))
    )
    (net (code "16") (name "D0") (class "Default")
      (node (ref "H5") (pin "2") (pinfunction "2_2") (pintype "unspecified"))
      (node (ref "J2") (pin "2") (pinfunction "D0/RX_2") (pintype "unspecified"))
    )
    (net (code "17") (name "D1") (class "Default")
      (node (ref "H5") (pin "1") (pinfunction "1_1") (pintype "unspecified"))
      (node (ref "J2") (pin "1") (pinfunction "D1/TX_1") (pintype "unspecified"))
    )
    (net (code "18") (name "D2") (class "Default")
      (node (ref "H5") (pin "5") (pinfunction "5_5") (pintype "unspecified"))
      (node (ref "J2") (pin "5") (pinfunction "D2/INT0_5") (pintype "unspecified"))
      (node (ref "SENS_2") (pin "2") (pinfunction "2_2") (pintype "unspecified"))
      (node (ref "SW2") (pin "1") (pinfunction "1_1") (pintype "unspecified"))
      (node (ref "SW2") (pin "2") (pinfunction "2_2") (pintype "unspecified"))
    )
    (net (code "19") (name "D3") (class "Default")
      (node (ref "H5") (pin "6") (pinfunction "6_6") (pintype "unspecified"))
      (node (ref "J2") (pin "6") (pinfunction "D3/INT1_6") (pintype "unspecified"))
      (node (ref "SENS_3") (pin "2") (pinfunction "2_2") (pintype "unspecified"))
      (node (ref "SW3") (pin "1") (pinfunction "1_1") (pintype "unspecified"))
      (node (ref "SW3") (pin "2") (pinfunction "2_2") (pintype "unspecified"))
    )
    (net (code "20") (name "D4") (class "Default")
      (node (ref "ALD") (pin "1") (pinfunction "A_1") (pintype "input"))
      (node (ref "AQ") (pin "1") (pinfunction "G_1") (pintype "unspecified"))
      (node (ref "ARG") (pin "2") (pinfunction "2_2") (pintype "input"))
      (node (ref "H5") (pin "7") (pinfunction "7_7") (pintype "unspecified"))
      (node (ref "J2") (pin "7") (pinfunction "D4/T0_7") (pintype "unspecified"))
      (node (ref "OUT_4") (pin "1") (pinfunction "1_1") (pintype "unspecified"))
    )
    (net (code "21") (name "D5") (class "Default")
      (node (ref "BLD") (pin "1") (pinfunction "A_1") (pintype "input"))
      (node (ref "BQ") (pin "1") (pinfunction "G_1") (pintype "unspecified"))
      (node (ref "BRG") (pin "2") (pinfunction "2_2") (pintype "input"))
      (node (ref "H5") (pin "8") (pinfunction "8_8") (pintype "unspecified"))
      (node (ref "J2") (pin "8") (pinfunction "D5/T1_8") (pintype "unspecified"))
      (node (ref "OUT_5") (pin "1") (pinfunction "1_1") (pintype "unspecified"))
    )
    (net (code "22") (name "D6") (class "Default")
      (node (ref "CLD") (pin "1") (pinfunction "A_1") (pintype "input"))
      (node (ref "CQ") (pin "1") (pinfunction "G_1") (pintype "unspecified"))
      (node (ref "CRG") (pin "2") (pinfunction "2_2") (pintype "input"))
      (node (ref "H5") (pin "9") (pinfunction "9_9") (pintype "unspecified"))
      (node (ref "J2") (pin "9") (pinfunction "D6/AIN0_9") (pintype "unspecified"))
      (node (ref "OUT_6") (pin "1") (pinfunction "1_1") (pintype "unspecified"))
    )
    (net (code "23") (name "D7") (class "Default")
      (node (ref "DLD") (pin "1") (pinfunction "A_1") (pintype "input"))
      (node (ref "DQ") (pin "1") (pinfunction "G_1") (pintype "unspecified"))
      (node (ref "DRG") (pin "2") (pinfunction "2_2") (pintype "input"))
      (node (ref "H5") (pin "10") (pinfunction "10_10") (pintype "unspecified"))
      (node (ref "J2") (pin "10") (pinfunction "D7/AIN1_10") (pintype "unspecified"))
      (node (ref "OUT_7") (pin "1") (pinfunction "1_1") (pintype "unspecified"))
    )
    (net (code "24") (name "D8") (class "Default")
      (node (ref "ELD") (pin "1") (pinfunction "A_1") (pintype "input"))
      (node (ref "EQ") (pin "1") (pinfunction "G_1") (pintype "unspecified"))
      (node (ref "ERG") (pin "2") (pinfunction "2_2") (pintype "input"))
      (node (ref "H5") (pin "11") (pinfunction "11_11") (pintype "unspecified"))
      (node (ref "J2") (pin "11") (pinfunction "D8/ICP_11") (pintype "unspecified"))
      (node (ref "OUT_8") (pin "1") (pinfunction "1_1") (pintype "unspecified"))
    )
    (net (code "25") (name "D9") (class "Default")
      (node (ref "FLD") (pin "1") (pinfunction "A_1") (pintype "input"))
      (node (ref "FQ") (pin "1") (pinfunction "G_1") (pintype "unspecified"))
      (node (ref "FRG") (pin "2") (pinfunction "2_2") (pintype "input"))
      (node (ref "H5") (pin "12") (pinfunction "12_12") (pintype "unspecified"))
      (node (ref "J2") (pin "12") (pinfunction "D9/0C1_12") (pintype "unspecified"))
      (node (ref "OUT_9") (pin "1") (pinfunction "1_1") (pintype "unspecified"))
    )
    (net (code "26") (name "D10") (class "Default")
      (node (ref "GLD") (pin "1") (pinfunction "A_1") (pintype "input"))
      (node (ref "GQ") (pin "1") (pinfunction "G_1") (pintype "unspecified"))
      (node (ref "GRG") (pin "2") (pinfunction "2_2") (pintype "input"))
      (node (ref "H5") (pin "13") (pinfunction "13_13") (pintype "unspecified"))
      (node (ref "J2") (pin "13") (pinfunction "D10_13") (pintype "unspecified"))
      (node (ref "OUT_10") (pin "1") (pinfunction "1_1") (pintype "unspecified"))
    )
    (net (code "27") (name "D11") (class "Default")
      (node (ref "H5") (pin "14") (pinfunction "14_14") (pintype "unspecified"))
      (node (ref "HLD") (pin "1") (pinfunction "A_1") (pintype "input"))
      (node (ref "HQ") (pin "1") (pinfunction "G_1") (pintype "unspecified"))
      (node (ref "HRG") (pin "2") (pinfunction "2_2") (pintype "input"))
      (node (ref "J2") (pin "14") (pinfunction "D11/MOSI_14") (pintype "unspecified"))
      (node (ref "OUT_11") (pin "1") (pinfunction "1_1") (pintype "unspecified"))
    )
    (net (code "28") (name "D13") (class "Default")
      (node (ref "H4") (pin "15") (pinfunction "15_15") (pintype "unspecified"))
      (node (ref "J2") (pin "16") (pinfunction "SCK/D13_16") (pintype "unspecified"))
    )
    (net (code "29") (name "GND") (class "Default")
      (node (ref "AQ") (pin "2") (pinfunction "S_2") (pintype "unspecified"))
      (node (ref "ARG") (pin "1") (pinfunction "1_1") (pintype "input"))
      (node (ref "ARL") (pin "1") (pinfunction "1_1") (pintype "input"))
      (node (ref "BQ") (pin "2") (pinfunction "S_2") (pintype "unspecified"))
      (node (ref "BRG") (pin "1") (pinfunction "1_1") (pintype "input"))
      (node (ref "BRL") (pin "1") (pinfunction "1_1") (pintype "input"))
      (node (ref "BUZZER1") (pin "2") (pinfunction "2_2") (pintype "unspecified"))
      (node (ref "C1") (pin "2") (pinfunction "2_2") (pintype "input"))
      (node (ref "C10") (pin "1") (pinfunction "1_1") (pintype "unspecified"))
      (node (ref "C11") (pin "1") (pinfunction "1_1") (pintype "unspecified"))
      (node (ref "C2") (pin "2") (pinfunction "2_2") (pintype "input"))
      (node (ref "CQ") (pin "2") (pinfunction "S_2") (pintype "unspecified"))
      (node (ref "CRG") (pin "1") (pinfunction "1_1") (pintype "input"))
      (node (ref "CRL") (pin "1") (pinfunction "1_1") (pintype "input"))
      (node (ref "DC1") (pin "2") (pinfunction "2_2") (pintype "unspecified"))
      (node (ref "DC1") (pin "3") (pinfunction "3_3") (pintype "unspecified"))
      (node (ref "DQ") (pin "2") (pinfunction "S_2") (pintype "unspecified"))
      (node (ref "DRG") (pin "1") (pinfunction "1_1") (pintype "input"))
      (node (ref "DRL") (pin "1") (pinfunction "1_1") (pintype "input"))
      (node (ref "EQ") (pin "2") (pinfunction "S_2") (pintype "unspecified"))
      (node (ref "ERG") (pin "1") (pinfunction "1_1") (pintype "input"))
      (node (ref "ERL") (pin "1") (pinfunction "1_1") (pintype "input"))
      (node (ref "EX_V") (pin "2") (pinfunction "2_2") (pintype "unspecified"))
      (node (ref "FQ") (pin "2") (pinfunction "S_2") (pintype "unspecified"))
      (node (ref "FRG") (pin "1") (pinfunction "1_1") (pintype "input"))
      (node (ref "FRL") (pin "1") (pinfunction "1_1") (pintype "input"))
      (node (ref "GQ") (pin "2") (pinfunction "S_2") (pintype "unspecified"))
      (node (ref "GRG") (pin "1") (pinfunction "1_1") (pintype "input"))
      (node (ref "GRL") (pin "1") (pinfunction "1_1") (pintype "input"))
      (node (ref "H1") (pin "6") (pinfunction "6_6") (pintype "input"))
      (node (ref "H11") (pin "6") (pinfunction "6_6") (pintype "input"))
      (node (ref "H2") (pin "6") (pinfunction "6_6") (pintype "input"))
      (node (ref "H3") (pin "6") (pinfunction "6_6") (pintype "input"))
      (node (ref "H4") (pin "2") (pinfunction "2_2") (pintype "unspecified"))
      (node (ref "H5") (pin "4") (pinfunction "4_4") (pintype "unspecified"))
      (node (ref "H6") (pin "6") (pinfunction "6_6") (pintype "input"))
      (node (ref "HQ") (pin "2") (pinfunction "S_2") (pintype "unspecified"))
      (node (ref "HRG") (pin "1") (pinfunction "1_1") (pintype "input"))
      (node (ref "HRL") (pin "1") (pinfunction "1_1") (pintype "input"))
      (node (ref "J2") (pin "29") (pinfunction "GND_29") (pintype "unspecified"))
      (node (ref "J2") (pin "4") (pinfunction "GND_4") (pintype "unspecified"))
      (node (ref "OLED") (pin "2") (pinfunction "GND_2") (pintype "passive"))
      (node (ref "OUT_10") (pin "2") (pinfunction "2_2") (pintype "unspecified"))
      (node (ref "OUT_11") (pin "2") (pinfunction "2_2") (pintype "unspecified"))
      (node (ref "OUT_4") (pin "2") (pinfunction "2_2") (pintype "unspecified"))
      (node (ref "OUT_5") (pin "2") (pinfunction "2_2") (pintype "unspecified"))
      (node (ref "OUT_6") (pin "2") (pinfunction "2_2") (pintype "unspecified"))
      (node (ref "OUT_7") (pin "2") (pinfunction "2_2") (pintype "unspecified"))
      (node (ref "OUT_8") (pin "2") (pinfunction "2_2") (pintype "unspecified"))
      (node (ref "OUT_9") (pin "2") (pinfunction "2_2") (pintype "unspecified"))
      (node (ref "P2") (pin "1") (pinfunction "1_1") (pintype "input"))
      (node (ref "P3") (pin "1") (pinfunction "1_1") (pintype "input"))
      (node (ref "RL12V") (pin "2") (pinfunction "2_2") (pintype "input"))
      (node (ref "RL5VB") (pin "2") (pinfunction "2_2") (pintype "input"))
      (node (ref "SENS_2") (pin "3") (pinfunction "3_3") (pintype "unspecified"))
      (node (ref "SENS_3") (pin "3") (pinfunction "3_3") (pintype "unspecified"))
      (node (ref "SENS_A0") (pin "3") (pinfunction "3_3") (pintype "unspecified"))
      (node (ref "SENS_A1") (pin "3") (pinfunction "3_3") (pintype "unspecified"))
      (node (ref "SENS_A2") (pin "3") (pinfunction "3_3") (pintype "unspecified"))
      (node (ref "SENS_A3") (pin "3") (pinfunction "3_3") (pintype "unspecified"))
      (node (ref "SW2") (pin "3") (pinfunction "3_3") (pintype "unspecified"))
      (node (ref "SW2") (pin "4") (pinfunction "4_4") (pintype "unspecified"))
      (node (ref "SW3") (pin "3") (pinfunction "3_3") (pintype "unspecified"))
      (node (ref "SW3") (pin "4") (pinfunction "4_4") (pintype "unspecified"))
      (node (ref "SWA0") (pin "3") (pinfunction "3_3") (pintype "unspecified"))
      (node (ref "SWA0") (pin "4") (pinfunction "4_4") (pintype "unspecified"))
      (node (ref "SWA1") (pin "3") (pinfunction "3_3") (pintype "unspecified"))
      (node (ref "SWA1") (pin "4") (pinfunction "4_4") (pintype "unspecified"))
      (node (ref "SWA2") (pin "3") (pinfunction "3_3") (pintype "unspecified"))
      (node (ref "SWA2") (pin "4") (pinfunction "4_4") (pintype "unspecified"))
      (node (ref "SWA3") (pin "3") (pinfunction "3_3") (pintype "unspecified"))
      (node (ref "SWA3") (pin "4") (pinfunction "4_4") (pintype "unspecified"))
      (node (ref "U3") (pin "3") (pinfunction "GND_3") (pintype "unspecified"))
      (node (ref "U5") (pin "2") (pinfunction "GND_2") (pintype "unspecified"))
    )
    (net (code "30") (name "Net-(ADM-A)") (class "Default")
      (node (ref "ACM") (pin "2") (pinfunction "2_2") (pintype "input"))
      (node (ref "ACON") (pin "2") (pinfunction "2_2") (pintype "unspecified"))
      (node (ref "ADM") (pin "2") (pinfunction "A_2") (pintype "unspecified"))
      (node (ref "AQ") (pin "3") (pinfunction "D_3") (pintype "unspecified"))
    )
    (net (code "31") (name "Net-(ADM-C)") (class "Default")
      (node (ref "ACM") (pin "1") (pinfunction "1_1") (pintype "input"))
      (node (ref "ACON") (pin "1") (pinfunction "1_1") (pintype "unspecified"))
      (node (ref "ADM") (pin "1") (pinfunction "C_1") (pintype "unspecified"))
      (node (ref "AJ12V") (pin "1") (pinfunction "1_1") (pintype "bidirectional"))
      (node (ref "AJ5V") (pin "1") (pinfunction "1_1") (pintype "bidirectional"))
    )
    (net (code "32") (name "Net-(ALD-C)") (class "Default")
      (node (ref "ALD") (pin "2") (pinfunction "C_2") (pintype "input"))
      (node (ref "ARL") (pin "2") (pinfunction "2_2") (pintype "input"))
    )
    (net (code "33") (name "Net-(BDM-A)") (class "Default")
      (node (ref "BCM") (pin "2") (pinfunction "2_2") (pintype "input"))
      (node (ref "BCON") (pin "2") (pinfunction "2_2") (pintype "unspecified"))
      (node (ref "BDM") (pin "2") (pinfunction "A_2") (pintype "unspecified"))
      (node (ref "BQ") (pin "3") (pinfunction "D_3") (pintype "unspecified"))
    )
    (net (code "34") (name "Net-(BDM-C)") (class "Default")
      (node (ref "BCM") (pin "1") (pinfunction "1_1") (pintype "input"))
      (node (ref "BCON") (pin "1") (pinfunction "1_1") (pintype "unspecified"))
      (node (ref "BDM") (pin "1") (pinfunction "C_1") (pintype "unspecified"))
      (node (ref "BJ12V") (pin "1") (pinfunction "1_1") (pintype "bidirectional"))
      (node (ref "BJ5V") (pin "1") (pinfunction "1_1") (pintype "bidirectional"))
    )
    (net (code "35") (name "Net-(BLD-C)") (class "Default")
      (node (ref "BLD") (pin "2") (pinfunction "C_2") (pintype "input"))
      (node (ref "BRL") (pin "2") (pinfunction "2_2") (pintype "input"))
    )
    (net (code "36") (name "Net-(CDM-A)") (class "Default")
      (node (ref "CCM") (pin "2") (pinfunction "2_2") (pintype "input"))
      (node (ref "CCON") (pin "2") (pinfunction "2_2") (pintype "unspecified"))
      (node (ref "CDM") (pin "2") (pinfunction "A_2") (pintype "unspecified"))
      (node (ref "CQ") (pin "3") (pinfunction "D_3") (pintype "unspecified"))
    )
    (net (code "37") (name "Net-(CDM-C)") (class "Default")
      (node (ref "CCM") (pin "1") (pinfunction "1_1") (pintype "input"))
      (node (ref "CCON") (pin "1") (pinfunction "1_1") (pintype "unspecified"))
      (node (ref "CDM") (pin "1") (pinfunction "C_1") (pintype "unspecified"))
      (node (ref "CJ12V") (pin "1") (pinfunction "1_1") (pintype "bidirectional"))
      (node (ref "CJ5V") (pin "1") (pinfunction "1_1") (pintype "bidirectional"))
    )
    (net (code "38") (name "Net-(CLD-C)") (class "Default")
      (node (ref "CLD") (pin "2") (pinfunction "C_2") (pintype "input"))
      (node (ref "CRL") (pin "2") (pinfunction "2_2") (pintype "input"))
    )
    (net (code "39") (name "Net-(DDM-A)") (class "Default")
      (node (ref "DCM") (pin "2") (pinfunction "2_2") (pintype "input"))
      (node (ref "DCON") (pin "2") (pinfunction "2_2") (pintype "unspecified"))
      (node (ref "DDM") (pin "2") (pinfunction "A_2") (pintype "unspecified"))
      (node (ref "DQ") (pin "3") (pinfunction "D_3") (pintype "unspecified"))
    )
    (net (code "40") (name "Net-(DDM-C)") (class "Default")
      (node (ref "DCM") (pin "1") (pinfunction "1_1") (pintype "input"))
      (node (ref "DCON") (pin "1") (pinfunction "1_1") (pintype "unspecified"))
      (node (ref "DDM") (pin "1") (pinfunction "C_1") (pintype "unspecified"))
      (node (ref "DJ12V") (pin "1") (pinfunction "1_1") (pintype "bidirectional"))
      (node (ref "DJ5V") (pin "1") (pinfunction "1_1") (pintype "bidirectional"))
    )
    (net (code "41") (name "Net-(DLD-C)") (class "Default")
      (node (ref "DLD") (pin "2") (pinfunction "C_2") (pintype "input"))
      (node (ref "DRL") (pin "2") (pinfunction "2_2") (pintype "input"))
    )
    (net (code "42") (name "Net-(EDM-A)") (class "Default")
      (node (ref "ECM") (pin "2") (pinfunction "2_2") (pintype "input"))
      (node (ref "ECON") (pin "2") (pinfunction "2_2") (pintype "unspecified"))
      (node (ref "EDM") (pin "2") (pinfunction "A_2") (pintype "unspecified"))
      (node (ref "EQ") (pin "3") (pinfunction "D_3") (pintype "unspecified"))
    )
    (net (code "43") (name "Net-(EDM-C)") (class "Default")
      (node (ref "ECM") (pin "1") (pinfunction "1_1") (pintype "input"))
      (node (ref "ECON") (pin "1") (pinfunction "1_1") (pintype "unspecified"))
      (node (ref "EDM") (pin "1") (pinfunction "C_1") (pintype "unspecified"))
      (node (ref "EJ12V") (pin "1") (pinfunction "1_1") (pintype "bidirectional"))
      (node (ref "EJ5V") (pin "1") (pinfunction "1_1") (pintype "bidirectional"))
    )
    (net (code "44") (name "Net-(ELD-C)") (class "Default")
      (node (ref "ELD") (pin "2") (pinfunction "C_2") (pintype "input"))
      (node (ref "ERL") (pin "2") (pinfunction "2_2") (pintype "input"))
    )
    (net (code "45") (name "Net-(FDM-A)") (class "Default")
      (node (ref "FCM") (pin "2") (pinfunction "2_2") (pintype "input"))
      (node (ref "FCON") (pin "2") (pinfunction "2_2") (pintype "unspecified"))
      (node (ref "FDM") (pin "2") (pinfunction "A_2") (pintype "unspecified"))
      (node (ref "FQ") (pin "3") (pinfunction "D_3") (pintype "unspecified"))
    )
    (net (code "46") (name "Net-(FDM-C)") (class "Default")
      (node (ref "FCM") (pin "1") (pinfunction "1_1") (pintype "input"))
      (node (ref "FCON") (pin "1") (pinfunction "1_1") (pintype "unspecified"))
      (node (ref "FDM") (pin "1") (pinfunction "C_1") (pintype "unspecified"))
      (node (ref "FJ12V") (pin "1") (pinfunction "1_1") (pintype "bidirectional"))
      (node (ref "FJ5V") (pin "1") (pinfunction "1_1") (pintype "bidirectional"))
    )
    (net (code "47") (name "Net-(FLD-C)") (class "Default")
      (node (ref "FLD") (pin "2") (pinfunction "C_2") (pintype "input"))
      (node (ref "FRL") (pin "2") (pinfunction "2_2") (pintype "input"))
    )
    (net (code "48") (name "Net-(GDM-A)") (class "Default")
      (node (ref "GCM") (pin "2") (pinfunction "2_2") (pintype "input"))
      (node (ref "GCON") (pin "2") (pinfunction "2_2") (pintype "unspecified"))
      (node (ref "GDM") (pin "2") (pinfunction "A_2") (pintype "unspecified"))
      (node (ref "GQ") (pin "3") (pinfunction "D_3") (pintype "unspecified"))
    )
    (net (code "49") (name "Net-(GDM-C)") (class "Default")
      (node (ref "GCM") (pin "1") (pinfunction "1_1") (pintype "input"))
      (node (ref "GCON") (pin "1") (pinfunction "1_1") (pintype "unspecified"))
      (node (ref "GDM") (pin "1") (pinfunction "C_1") (pintype "unspecified"))
      (node (ref "GJ12V") (pin "1") (pinfunction "1_1") (pintype "bidirectional"))
      (node (ref "GJ5V") (pin "1") (pinfunction "1_1") (pintype "bidirectional"))
    )
    (net (code "50") (name "Net-(GLD-C)") (class "Default")
      (node (ref "GLD") (pin "2") (pinfunction "C_2") (pintype "input"))
      (node (ref "GRL") (pin "2") (pinfunction "2_2") (pintype "input"))
    )
    (net (code "51") (name "Net-(H4-Pad3)") (class "Default")
      (node (ref "H4") (pin "3") (pinfunction "3_3") (pintype "unspecified"))
      (node (ref "J2") (pin "28") (pinfunction "RESET_28") (pintype "unspecified"))
    )
    (net (code "52") (name "Net-(H5-Pad3)") (class "Default")
      (node (ref "H5") (pin "3") (pinfunction "3_3") (pintype "unspecified"))
      (node (ref "J2") (pin "3") (pinfunction "RESET_3") (pintype "unspecified"))
    )
    (net (code "53") (name "Net-(HDM-A)") (class "Default")
      (node (ref "HCM") (pin "2") (pinfunction "2_2") (pintype "input"))
      (node (ref "HCON") (pin "2") (pinfunction "2_2") (pintype "unspecified"))
      (node (ref "HDM") (pin "2") (pinfunction "A_2") (pintype "unspecified"))
      (node (ref "HQ") (pin "3") (pinfunction "D_3") (pintype "unspecified"))
    )
    (net (code "54") (name "Net-(HDM-C)") (class "Default")
      (node (ref "HCM") (pin "1") (pinfunction "1_1") (pintype "input"))
      (node (ref "HCON") (pin "1") (pinfunction "1_1") (pintype "unspecified"))
      (node (ref "HDM") (pin "1") (pinfunction "C_1") (pintype "unspecified"))
      (node (ref "HJ12V") (pin "1") (pinfunction "1_1") (pintype "bidirectional"))
      (node (ref "HJ5V") (pin "1") (pinfunction "1_1") (pintype "bidirectional"))
    )
    (net (code "55") (name "Net-(HLD-C)") (class "Default")
      (node (ref "HLD") (pin "2") (pinfunction "C_2") (pintype "input"))
      (node (ref "HRL") (pin "2") (pinfunction "2_2") (pintype "input"))
    )
    (net (code "56") (name "Net-(J2-AREF)") (class "Default")
      (node (ref "H4") (pin "13") (pinfunction "13_13") (pintype "unspecified"))
      (node (ref "J2") (pin "18") (pinfunction "AREF_18") (pintype "unspecified"))
    )
    (net (code "57") (name "Net-(L12V-C)") (class "Default")
      (node (ref "L12V") (pin "2") (pinfunction "C_2") (pintype "input"))
      (node (ref "RL12V") (pin "1") (pinfunction "1_1") (pintype "input"))
    )
    (net (code "58") (name "Net-(LVB-C)") (class "Default")
      (node (ref "LVB") (pin "2") (pinfunction "C_2") (pintype "input"))
      (node (ref "RL5VB") (pin "1") (pinfunction "1_1") (pintype "input"))
    )
    (net (code "59") (name "Net-(U3-EN)") (class "Default")
      (node (ref "R1") (pin "1") (pinfunction "1_1") (pintype "input"))
      (node (ref "U3") (pin "1") (pinfunction "EN_1") (pintype "unspecified"))
    )
    (net (code "61") (name "unconnected-(H1-Pad2)") (class "Default")
      (node (ref "H1") (pin "2") (pinfunction "2_2") (pintype "input"))
    )
    (net (code "62") (name "unconnected-(H1-Pad3)") (class "Default")
      (node (ref "H1") (pin "3") (pinfunction "3_3") (pintype "input"))
    )
    (net (code "63") (name "unconnected-(H1-Pad4)") (class "Default")
      (node (ref "H1") (pin "4") (pinfunction "4_4") (pintype "input"))
    )
    (net (code "64") (name "unconnected-(H1-Pad5)") (class "Default")
      (node (ref "H1") (pin "5") (pinfunction "5_5") (pintype "input"))
    )
    (net (code "65") (name "unconnected-(H2-Pad2)") (class "Default")
      (node (ref "H2") (pin "2") (pinfunction "2_2") (pintype "input"))
    )
    (net (code "66") (name "unconnected-(H2-Pad3)") (class "Default")
      (node (ref "H2") (pin "3") (pinfunction "3_3") (pintype "input"))
    )
    (net (code "67") (name "unconnected-(H2-Pad4)") (class "Default")
      (node (ref "H2") (pin "4") (pinfunction "4_4") (pintype "input"))
    )
    (net (code "68") (name "unconnected-(H2-Pad5)") (class "Default")
      (node (ref "H2") (pin "5") (pinfunction "5_5") (pintype "input"))
    )
    (net (code "69") (name "unconnected-(H3-Pad2)") (class "Default")
      (node (ref "H3") (pin "2") (pinfunction "2_2") (pintype "input"))
    )
    (net (code "70") (name "unconnected-(H3-Pad3)") (class "Default")
      (node (ref "H3") (pin "3") (pinfunction "3_3") (pintype "input"))
    )
    (net (code "71") (name "unconnected-(H3-Pad4)") (class "Default")
      (node (ref "H3") (pin "4") (pinfunction "4_4") (pintype "input"))
    )
    (net (code "72") (name "unconnected-(H3-Pad5)") (class "Default")
      (node (ref "H3") (pin "5") (pinfunction "5_5") (pintype "input"))
    )
    (net (code "73") (name "unconnected-(H6-Pad2)") (class "Default")
      (node (ref "H6") (pin "2") (pinfunction "2_2") (pintype "input"))
    )
    (net (code "74") (name "unconnected-(H6-Pad3)") (class "Default")
      (node (ref "H6") (pin "3") (pinfunction "3_3") (pintype "input"))
    )
    (net (code "75") (name "unconnected-(H6-Pad4)") (class "Default")
      (node (ref "H6") (pin "4") (pinfunction "4_4") (pintype "input"))
    )
    (net (code "76") (name "unconnected-(H6-Pad5)") (class "Default")
      (node (ref "H6") (pin "5") (pinfunction "5_5") (pintype "input"))
    )
    (net (code "77") (name "unconnected-(H11-Pad2)") (class "Default")
      (node (ref "H11") (pin "2") (pinfunction "2_2") (pintype "input"))
    )
    (net (code "78") (name "unconnected-(H11-Pad3)") (class "Default")
      (node (ref "H11") (pin "3") (pinfunction "3_3") (pintype "input"))
    )
    (net (code "79") (name "unconnected-(H11-Pad4)") (class "Default")
      (node (ref "H11") (pin "4") (pinfunction "4_4") (pintype "input"))
    )
    (net (code "80") (name "unconnected-(H11-Pad5)") (class "Default")
      (node (ref "H11") (pin "5") (pinfunction "5_5") (pintype "input"))
    )
    (net (code "81") (name "unconnected-(P2-Pad4)") (class "Default")
      (node (ref "P2") (pin "4") (pinfunction "4_4") (pintype "input"))
    )
    (net (code "82") (name "unconnected-(P2-Pad5)") (class "Default")
      (node (ref "P2") (pin "5") (pinfunction "5_5") (pintype "input"))
    )
    (net (code "83") (name "unconnected-(P3-Pad4)") (class "Default")
      (node (ref "P3") (pin "4") (pinfunction "4_4") (pintype "input"))
    )
    (net (code "84") (name "unconnected-(P3-Pad5)") (class "Default")
      (node (ref "P3") (pin "5") (pinfunction "5_5") (pintype "input"))
    )
    (net (code "85") (name "unconnected-(U1-Pad1)") (class "Default")
      (node (ref "U1") (pin "1") (pinfunction "1_1") (pintype "unspecified"))
    )
    (net (code "86") (name "unconnected-(U1-Pad2)") (class "Default")
      (node (ref "U1") (pin "2") (pinfunction "2_2") (pintype "unspecified"))
    )
    (net (code "87") (name "unconnected-(U1-Pad3)") (class "Default")
      (node (ref "U1") (pin "3") (pinfunction "3_3") (pintype "unspecified"))
    )
    (net (code "88") (name "unconnected-(U1-Pad4)") (class "Default")
      (node (ref "U1") (pin "4") (pinfunction "4_4") (pintype "unspecified"))
    )
  )
)
